# gloria.net
KiCad netlist of a schematic drawn in EAGLE
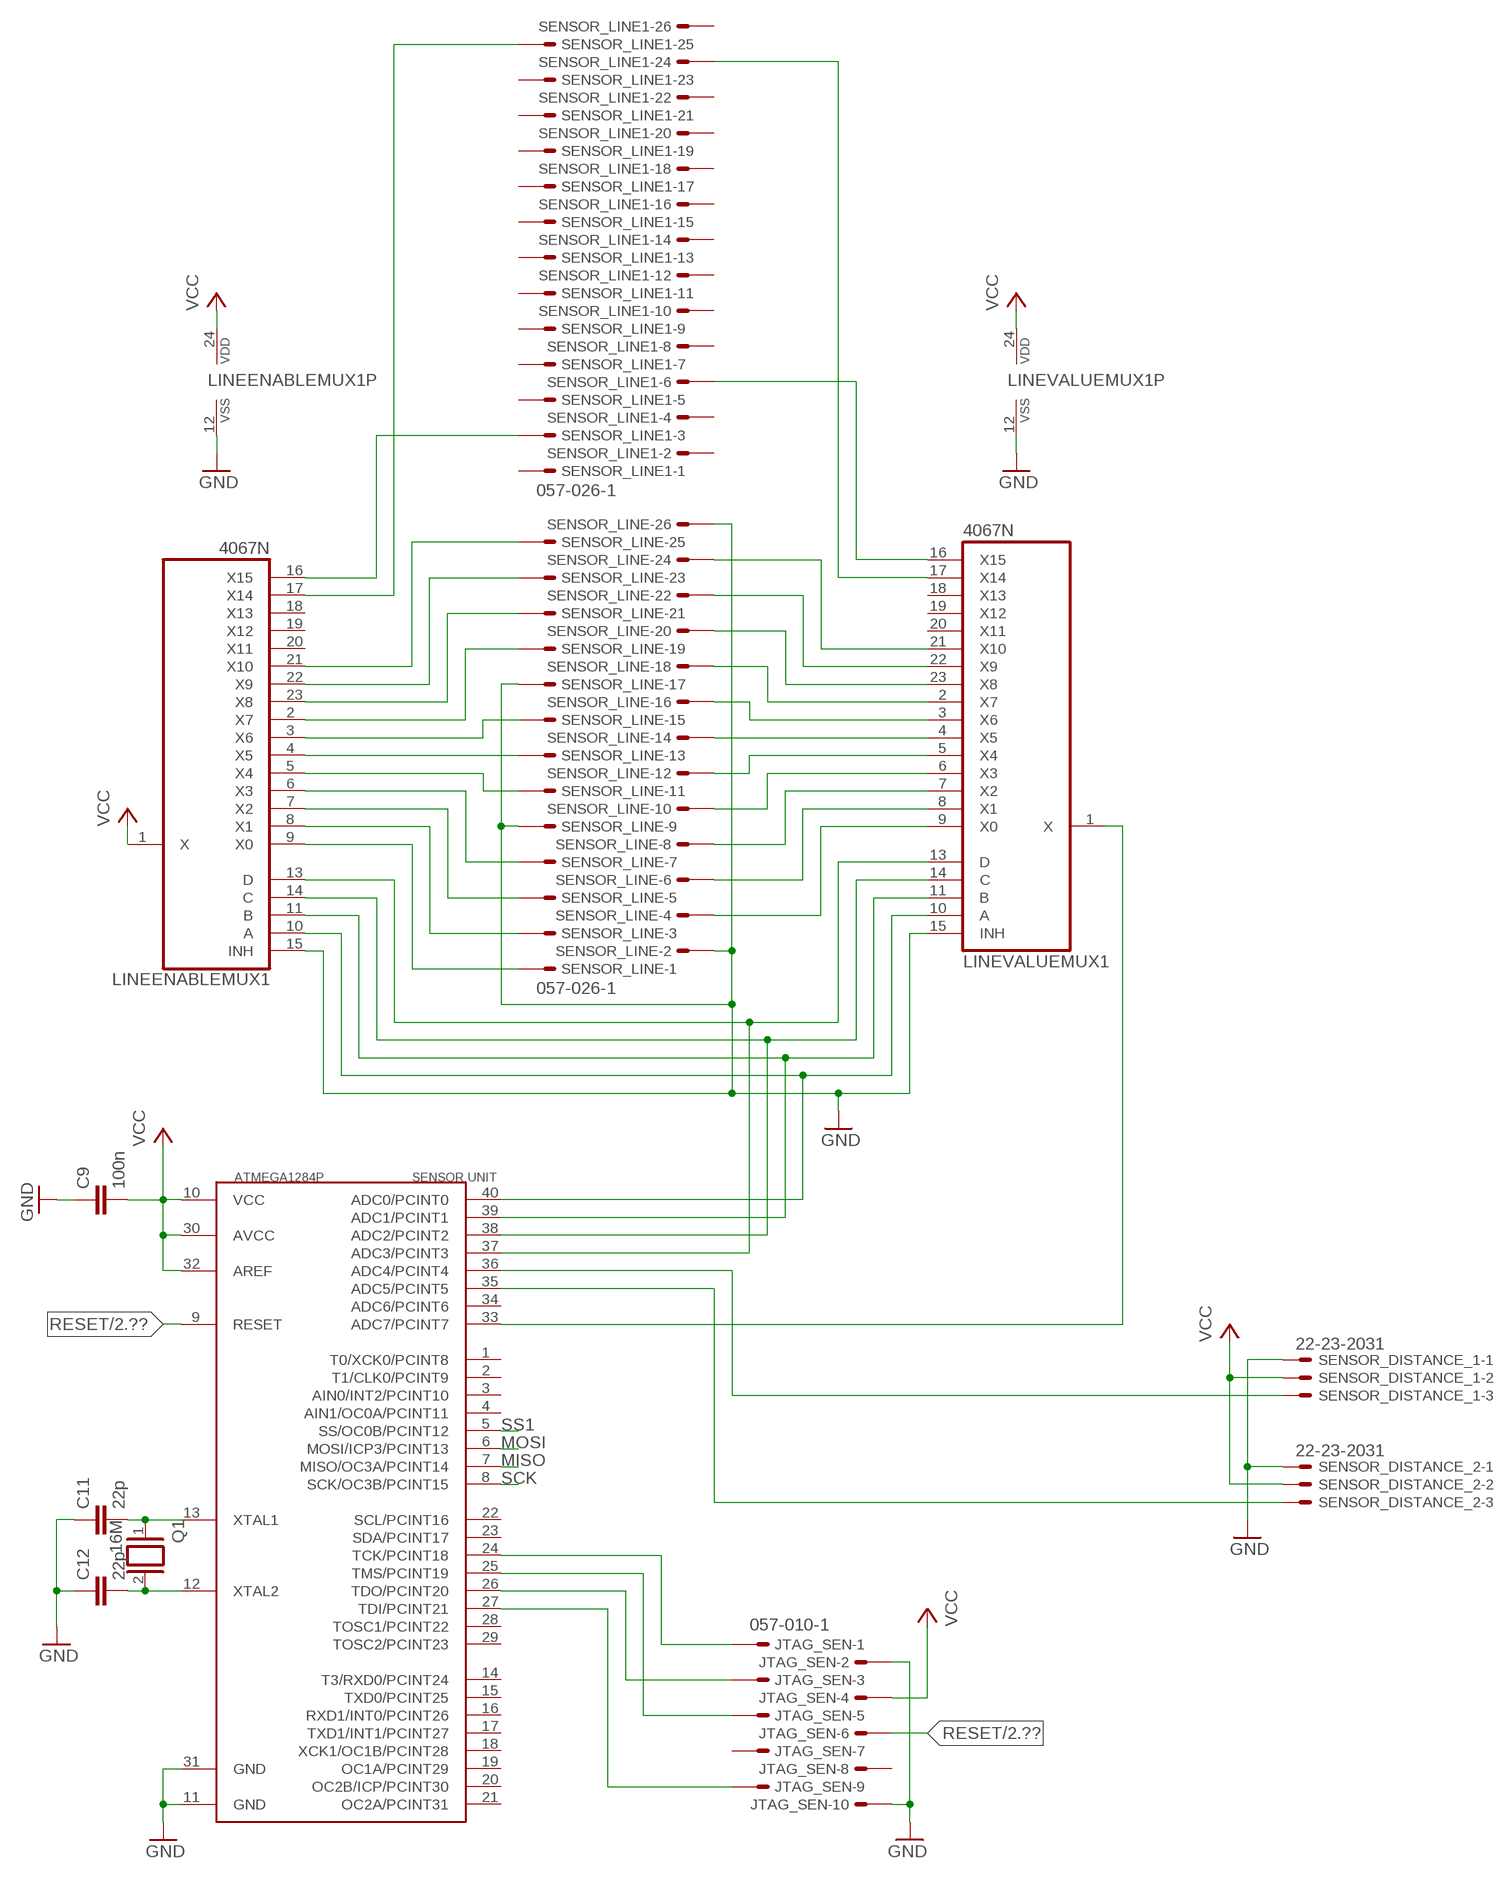
[diagram p0: schematic, sheet 1]
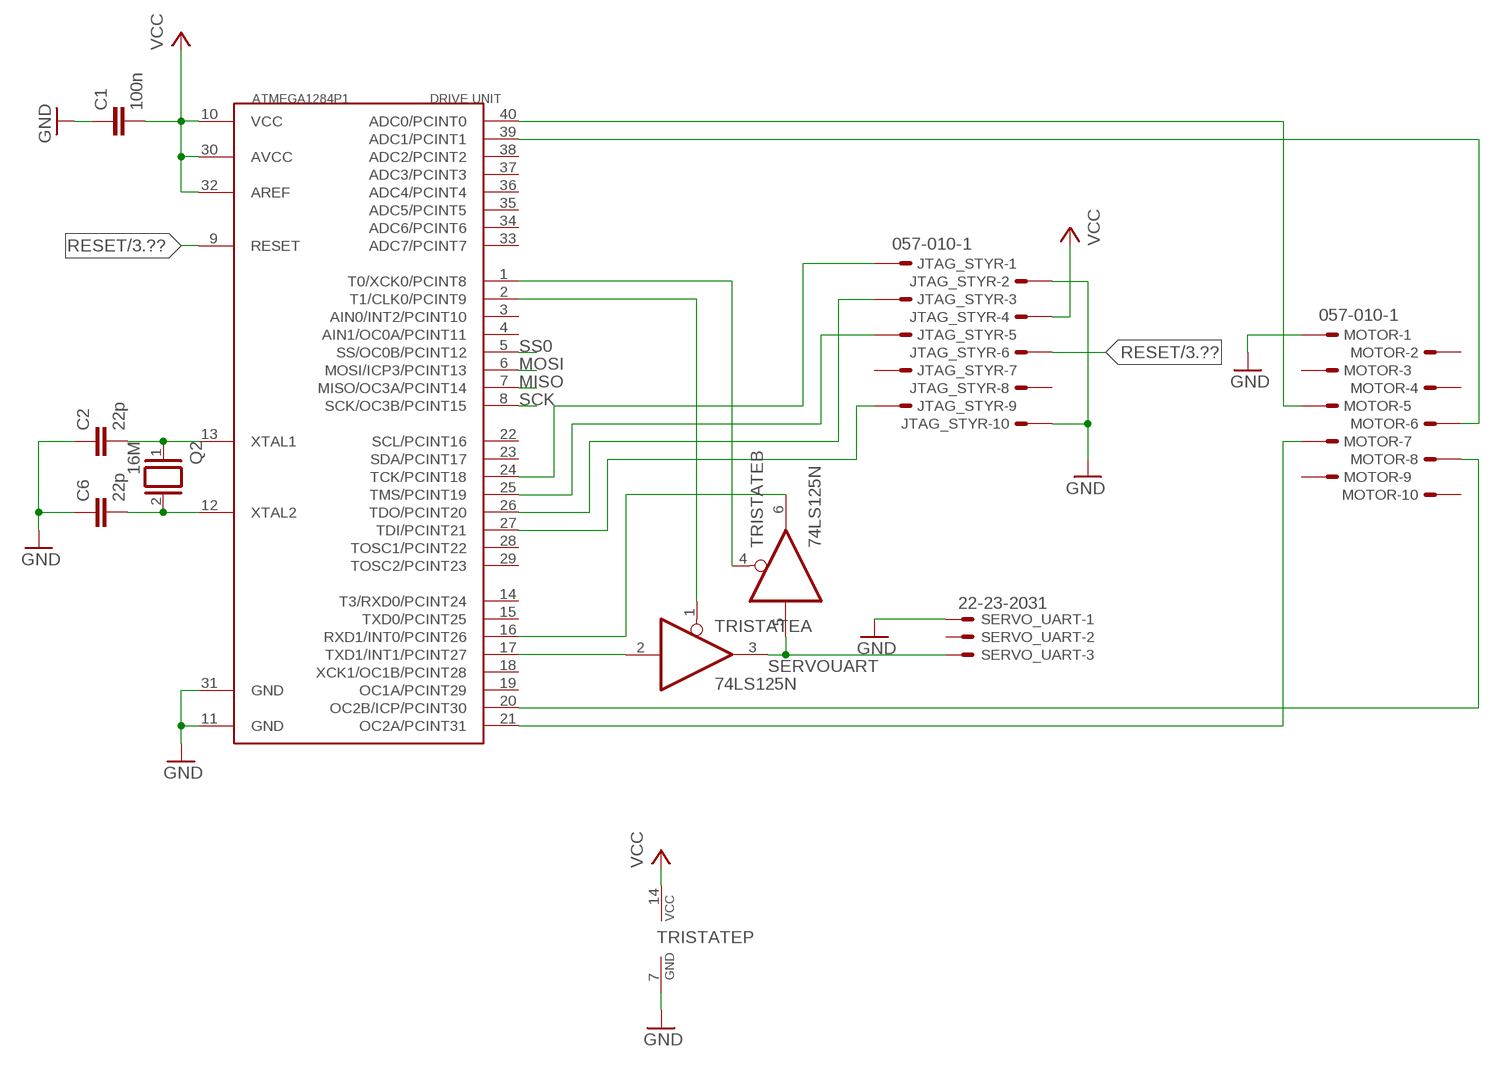
[diagram p1: schematic, sheet 2]
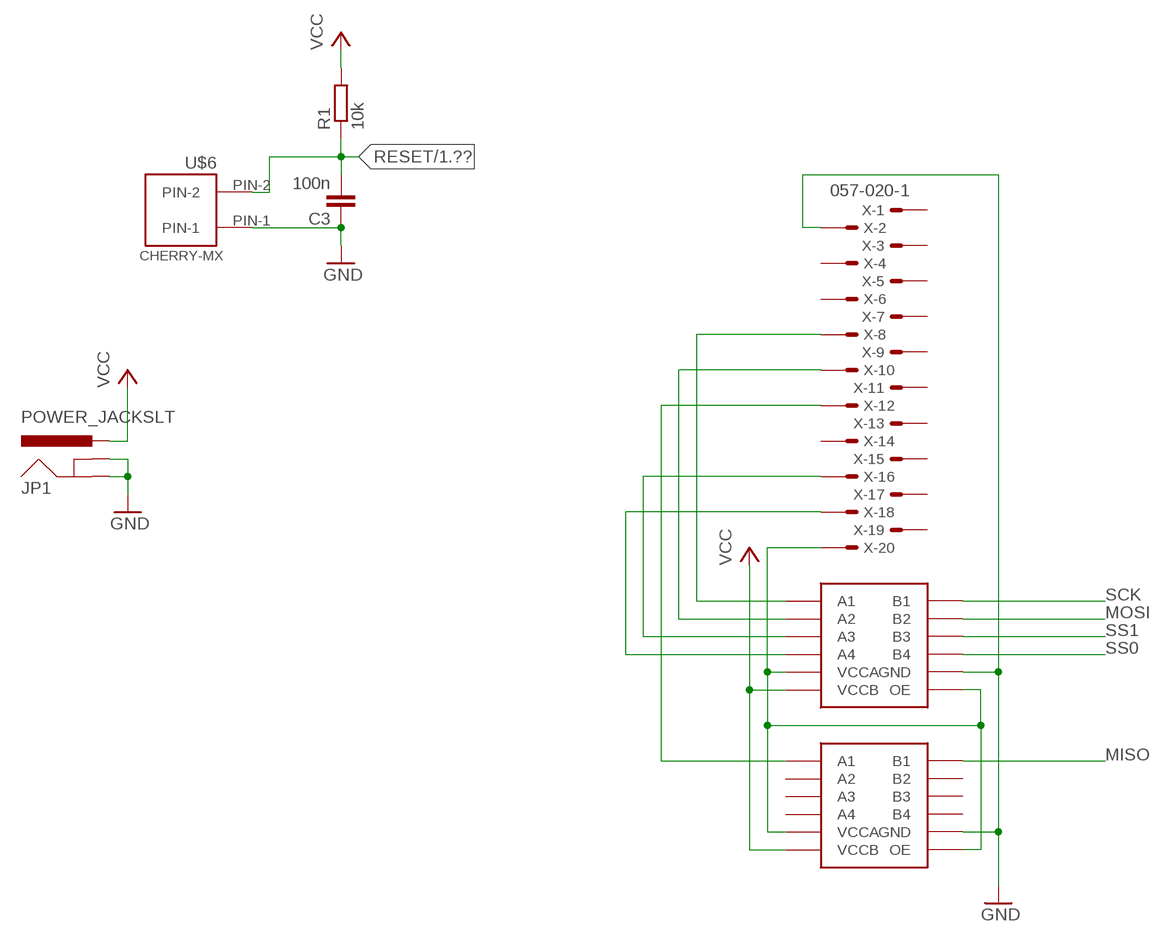
[diagram p2: schematic, sheet 3]

(export (version "E")
  (design (tool "Eeschema 10.0.6"))
  (components
    (comp (ref "ATMEGA1284P")
      (value "SENSOR UNIT")
      (footprint "eagle-import:DIL40")
      (libsource (lib "eagle-import") (part "MEGA1284P"))
    )
    (comp (ref "C9")
      (value "100n")
      (footprint "eagle-import:C025-024X044")
      (libsource (lib "eagle-import") (part "C-EU025-024X044"))
    )
    (comp (ref "C11")
      (value "22p")
      (footprint "eagle-import:C025-024X044")
      (libsource (lib "eagle-import") (part "C-EU025-024X044"))
    )
    (comp (ref "C12")
      (value "22p")
      (footprint "eagle-import:C025-024X044")
      (libsource (lib "eagle-import") (part "C-EU025-024X044"))
    )
    (comp (ref "JTAG_SEN")
      (value "057-010-1")
      (footprint "eagle-import:057-010-1")
      (libsource (lib "eagle-import") (part "057-010-1"))
    )
    (comp (ref "LINEENABLEMUX1")
      (value "4067N")
      (footprint "eagle-import:DIL24-6")
      (libsource (lib "eagle-import") (part "4067N"))
    )
    (comp (ref "LINEVALUEMUX1")
      (value "4067N")
      (footprint "eagle-import:DIL24-6")
      (libsource (lib "eagle-import") (part "4067N"))
    )
    (comp (ref "Q1")
      (value "16M")
      (footprint "eagle-import:QS")
      (libsource (lib "eagle-import") (part "XTAL/S"))
    )
    (comp (ref "SENSOR_DISTANCE_1")
      (value "22-23-2031")
      (footprint "eagle-import:22-23-2031")
      (fields (field (name "MF") "MOLEX"))
      (libsource (lib "eagle-import") (part "22-23-2031"))
    )
    (comp (ref "SENSOR_DISTANCE_2")
      (value "22-23-2031")
      (footprint "eagle-import:22-23-2031")
      (fields (field (name "MF") "MOLEX"))
      (libsource (lib "eagle-import") (part "22-23-2031"))
    )
    (comp (ref "SENSOR_LINE")
      (value "057-026-1")
      (footprint "eagle-import:057-026-1")
      (libsource (lib "eagle-import") (part "057-026-1"))
    )
    (comp (ref "SENSOR_LINE1")
      (value "057-026-1")
      (footprint "eagle-import:057-026-1")
      (libsource (lib "eagle-import") (part "057-026-1"))
    )
    (comp (ref "ATMEGA1284P1")
      (value "DRIVE UNIT")
      (footprint "eagle-import:DIL40")
      (libsource (lib "eagle-import") (part "MEGA1284P"))
    )
    (comp (ref "C1")
      (value "100n")
      (footprint "eagle-import:C025-024X044")
      (libsource (lib "eagle-import") (part "C-EU025-024X044"))
    )
    (comp (ref "C2")
      (value "22p")
      (footprint "eagle-import:C025-024X044")
      (libsource (lib "eagle-import") (part "C-EU025-024X044"))
    )
    (comp (ref "C6")
      (value "22p")
      (footprint "eagle-import:C025-024X044")
      (libsource (lib "eagle-import") (part "C-EU025-024X044"))
    )
    (comp (ref "JTAG_STYR")
      (value "057-010-1")
      (footprint "eagle-import:057-010-1")
      (libsource (lib "eagle-import") (part "057-010-1"))
    )
    (comp (ref "MOTOR")
      (value "057-010-1")
      (footprint "eagle-import:057-010-1")
      (libsource (lib "eagle-import") (part "057-010-1"))
    )
    (comp (ref "Q2")
      (value "16M")
      (footprint "eagle-import:QS")
      (libsource (lib "eagle-import") (part "XTAL/S"))
    )
    (comp (ref "SERVO_UART")
      (value "22-23-2031")
      (footprint "eagle-import:22-23-2031")
      (fields (field (name "MF") "MOLEX"))
      (libsource (lib "eagle-import") (part "22-23-2031"))
    )
    (comp (ref "TRISTATE")
      (value "74LS125N")
      (footprint "eagle-import:DIL14")
      (libsource (lib "eagle-import") (part "74125NLS"))
    )
    (comp (ref "C3")
      (value "100n")
      (footprint "eagle-import:C025-024X044")
      (libsource (lib "eagle-import") (part "C-EU025-024X044"))
    )
    (comp (ref "JP1")
      (value "POWER_JACKSLT")
      (footprint "eagle-import:POWER_JACK_SLOT")
      (libsource (lib "eagle-import") (part "POWER_JACKSLT"))
    )
    (comp (ref "R1")
      (value "10k")
      (footprint "eagle-import:0204V")
      (libsource (lib "eagle-import") (part "R-EU_0204/2V"))
    )
    (comp (ref "U$1")
      (value "TXB0104SOIC(D)")
      (footprint "eagle-import:TXB0104")
      (libsource (lib "eagle-import") (part "TXB0104SOIC(D)"))
    )
    (comp (ref "U$2")
      (value "TXB0104SOIC(D)")
      (footprint "eagle-import:TXB0104")
      (libsource (lib "eagle-import") (part "TXB0104SOIC(D)"))
    )
    (comp (ref "U$6")
      (value "CHERRY-MX-I")
      (footprint "eagle-import:CHERRY-MX-I")
      (libsource (lib "eagle-import") (part "CHERRY-MX-I"))
    )
    (comp (ref "X")
      (value "057-020-1")
      (footprint "eagle-import:057-020-1")
      (libsource (lib "eagle-import") (part "057-020-1"))
    )
  )
  (nets
    (net (code "1") (name "GND") (class "Default")
      (node (ref "ATMEGA1284P") (pin "11") (pinfunction "GND_11") (pintype "bidirectional"))
      (node (ref "ATMEGA1284P") (pin "31") (pinfunction "GND_31") (pintype "bidirectional"))
      (node (ref "ATMEGA1284P1") (pin "11") (pinfunction "GND_11") (pintype "bidirectional"))
      (node (ref "ATMEGA1284P1") (pin "31") (pinfunction "GND_31") (pintype "bidirectional"))
      (node (ref "C1") (pin "1") (pinfunction "1_1") (pintype "passive"))
      (node (ref "C11") (pin "1") (pinfunction "1_1") (pintype "passive"))
      (node (ref "C12") (pin "1") (pinfunction "1_1") (pintype "passive"))
      (node (ref "C2") (pin "1") (pinfunction "1_1") (pintype "passive"))
      (node (ref "C3") (pin "1") (pinfunction "1_1") (pintype "passive"))
      (node (ref "C6") (pin "1") (pinfunction "1_1") (pintype "passive"))
      (node (ref "C9") (pin "1") (pinfunction "1_1") (pintype "passive"))
      (node (ref "JP1") (pin "GND@1") (pinfunction "GNDBREAK_GND@1") (pintype "bidirectional"))
      (node (ref "JP1") (pin "GND@2") (pinfunction "GND_GND@2") (pintype "bidirectional"))
      (node (ref "JTAG_SEN") (pin "10") (pinfunction "S_10") (pintype "passive"))
      (node (ref "JTAG_SEN") (pin "2") (pinfunction "S_2") (pintype "passive"))
      (node (ref "JTAG_STYR") (pin "10") (pinfunction "S_10") (pintype "passive"))
      (node (ref "JTAG_STYR") (pin "2") (pinfunction "S_2") (pintype "passive"))
      (node (ref "LINEENABLEMUX1") (pin "12") (pinfunction "VSS_12") (pintype "power_in"))
      (node (ref "LINEENABLEMUX1") (pin "15") (pinfunction "INH_15") (pintype "input"))
      (node (ref "LINEVALUEMUX1") (pin "12") (pinfunction "VSS_12") (pintype "power_in"))
      (node (ref "LINEVALUEMUX1") (pin "15") (pinfunction "INH_15") (pintype "input"))
      (node (ref "MOTOR") (pin "1") (pinfunction "S_1") (pintype "passive"))
      (node (ref "SENSOR_DISTANCE_1") (pin "1") (pinfunction "S_1") (pintype "passive"))
      (node (ref "SENSOR_DISTANCE_2") (pin "1") (pinfunction "S_1") (pintype "passive"))
      (node (ref "SENSOR_LINE") (pin "17") (pinfunction "S_17") (pintype "passive"))
      (node (ref "SENSOR_LINE") (pin "2") (pinfunction "S_2") (pintype "passive"))
      (node (ref "SENSOR_LINE") (pin "26") (pinfunction "S_26") (pintype "passive"))
      (node (ref "SENSOR_LINE") (pin "9") (pinfunction "S_9") (pintype "passive"))
      (node (ref "SERVO_UART") (pin "1") (pinfunction "S_1") (pintype "passive"))
      (node (ref "TRISTATE") (pin "7") (pinfunction "GND_7") (pintype "power_in"))
      (node (ref "U$1") (pin "P$7") (pinfunction "GND_P$7") (pintype "bidirectional"))
      (node (ref "U$2") (pin "P$7") (pinfunction "GND_P$7") (pintype "bidirectional"))
      (node (ref "U$6") (pin "PIN-1") (pinfunction "PIN-1_PIN-1") (pintype "bidirectional"))
      (node (ref "X") (pin "2") (pinfunction "S_2") (pintype "passive"))
    )
    (net (code "2") (name "MISO") (class "Default")
      (node (ref "ATMEGA1284P") (pin "7") (pinfunction "MISO/OC3A/PCINT14_7") (pintype "bidirectional"))
      (node (ref "ATMEGA1284P1") (pin "7") (pinfunction "MISO/OC3A/PCINT14_7") (pintype "bidirectional"))
      (node (ref "U$2") (pin "P$13") (pinfunction "B1_P$13") (pintype "bidirectional"))
    )
    (net (code "3") (name "MOSI") (class "Default")
      (node (ref "ATMEGA1284P") (pin "6") (pinfunction "MOSI/ICP3/PCINT13_6") (pintype "bidirectional"))
      (node (ref "ATMEGA1284P1") (pin "6") (pinfunction "MOSI/ICP3/PCINT13_6") (pintype "bidirectional"))
      (node (ref "U$1") (pin "P$12") (pinfunction "B2_P$12") (pintype "bidirectional"))
    )
    (net (code "4") (name "Net-(ATMEGA1284P-ADC0{slash}PCINT0)") (class "Default")
      (node (ref "ATMEGA1284P") (pin "40") (pinfunction "ADC0/PCINT0_40") (pintype "bidirectional"))
      (node (ref "LINEENABLEMUX1") (pin "10") (pinfunction "A_10") (pintype "input"))
      (node (ref "LINEVALUEMUX1") (pin "10") (pinfunction "A_10") (pintype "input"))
    )
    (net (code "5") (name "Net-(ATMEGA1284P-ADC1{slash}PCINT1)") (class "Default")
      (node (ref "ATMEGA1284P") (pin "39") (pinfunction "ADC1/PCINT1_39") (pintype "bidirectional"))
      (node (ref "LINEENABLEMUX1") (pin "11") (pinfunction "B_11") (pintype "input"))
      (node (ref "LINEVALUEMUX1") (pin "11") (pinfunction "B_11") (pintype "input"))
    )
    (net (code "6") (name "Net-(ATMEGA1284P-ADC2{slash}PCINT2)") (class "Default")
      (node (ref "ATMEGA1284P") (pin "38") (pinfunction "ADC2/PCINT2_38") (pintype "bidirectional"))
      (node (ref "LINEENABLEMUX1") (pin "14") (pinfunction "C_14") (pintype "input"))
      (node (ref "LINEVALUEMUX1") (pin "14") (pinfunction "C_14") (pintype "input"))
    )
    (net (code "7") (name "Net-(ATMEGA1284P-ADC3{slash}PCINT3)") (class "Default")
      (node (ref "ATMEGA1284P") (pin "37") (pinfunction "ADC3/PCINT3_37") (pintype "bidirectional"))
      (node (ref "LINEENABLEMUX1") (pin "13") (pinfunction "D_13") (pintype "input"))
      (node (ref "LINEVALUEMUX1") (pin "13") (pinfunction "D_13") (pintype "input"))
    )
    (net (code "8") (name "Net-(ATMEGA1284P-ADC4{slash}PCINT4)") (class "Default")
      (node (ref "ATMEGA1284P") (pin "36") (pinfunction "ADC4/PCINT4_36") (pintype "bidirectional"))
      (node (ref "SENSOR_DISTANCE_1") (pin "3") (pinfunction "S_3") (pintype "passive"))
    )
    (net (code "9") (name "Net-(ATMEGA1284P-ADC5{slash}PCINT5)") (class "Default")
      (node (ref "ATMEGA1284P") (pin "35") (pinfunction "ADC5/PCINT5_35") (pintype "bidirectional"))
      (node (ref "SENSOR_DISTANCE_2") (pin "3") (pinfunction "S_3") (pintype "passive"))
    )
    (net (code "10") (name "Net-(ATMEGA1284P-ADC7{slash}PCINT7)") (class "Default")
      (node (ref "ATMEGA1284P") (pin "33") (pinfunction "ADC7/PCINT7_33") (pintype "bidirectional"))
      (node (ref "LINEVALUEMUX1") (pin "1") (pinfunction "X_1") (pintype "output"))
    )
    (net (code "11") (name "Net-(ATMEGA1284P-TCK{slash}PCINT18)") (class "Default")
      (node (ref "ATMEGA1284P") (pin "24") (pinfunction "TCK/PCINT18_24") (pintype "bidirectional"))
      (node (ref "JTAG_SEN") (pin "1") (pinfunction "S_1") (pintype "passive"))
    )
    (net (code "12") (name "Net-(ATMEGA1284P-TDI{slash}PCINT21)") (class "Default")
      (node (ref "ATMEGA1284P") (pin "27") (pinfunction "TDI/PCINT21_27") (pintype "bidirectional"))
      (node (ref "JTAG_SEN") (pin "9") (pinfunction "S_9") (pintype "passive"))
    )
    (net (code "13") (name "Net-(ATMEGA1284P-TDO{slash}PCINT20)") (class "Default")
      (node (ref "ATMEGA1284P") (pin "26") (pinfunction "TDO/PCINT20_26") (pintype "bidirectional"))
      (node (ref "JTAG_SEN") (pin "3") (pinfunction "S_3") (pintype "passive"))
    )
    (net (code "14") (name "Net-(ATMEGA1284P-TMS{slash}PCINT19)") (class "Default")
      (node (ref "ATMEGA1284P") (pin "25") (pinfunction "TMS/PCINT19_25") (pintype "bidirectional"))
      (node (ref "JTAG_SEN") (pin "5") (pinfunction "S_5") (pintype "passive"))
    )
    (net (code "15") (name "Net-(ATMEGA1284P-XTAL1)") (class "Default")
      (node (ref "ATMEGA1284P") (pin "13") (pinfunction "XTAL1_13") (pintype "bidirectional"))
      (node (ref "C11") (pin "2") (pinfunction "2_2") (pintype "passive"))
      (node (ref "Q1") (pin "1") (pinfunction "1_1") (pintype "passive"))
    )
    (net (code "16") (name "Net-(ATMEGA1284P-XTAL2)") (class "Default")
      (node (ref "ATMEGA1284P") (pin "12") (pinfunction "XTAL2_12") (pintype "bidirectional"))
      (node (ref "C12") (pin "2") (pinfunction "2_2") (pintype "passive"))
      (node (ref "Q1") (pin "2") (pinfunction "2_2") (pintype "passive"))
    )
    (net (code "17") (name "Net-(ATMEGA1284P1-ADC0{slash}PCINT0)") (class "Default")
      (node (ref "ATMEGA1284P1") (pin "40") (pinfunction "ADC0/PCINT0_40") (pintype "bidirectional"))
      (node (ref "MOTOR") (pin "5") (pinfunction "S_5") (pintype "passive"))
    )
    (net (code "18") (name "Net-(ATMEGA1284P1-ADC1{slash}PCINT1)") (class "Default")
      (node (ref "ATMEGA1284P1") (pin "39") (pinfunction "ADC1/PCINT1_39") (pintype "bidirectional"))
      (node (ref "MOTOR") (pin "6") (pinfunction "S_6") (pintype "passive"))
    )
    (net (code "19") (name "Net-(ATMEGA1284P1-OC2A{slash}PCINT31)") (class "Default")
      (node (ref "ATMEGA1284P1") (pin "21") (pinfunction "OC2A/PCINT31_21") (pintype "bidirectional"))
      (node (ref "MOTOR") (pin "7") (pinfunction "S_7") (pintype "passive"))
    )
    (net (code "20") (name "Net-(ATMEGA1284P1-OC2B{slash}ICP{slash}PCINT30)") (class "Default")
      (node (ref "ATMEGA1284P1") (pin "20") (pinfunction "OC2B/ICP/PCINT30_20") (pintype "bidirectional"))
      (node (ref "MOTOR") (pin "8") (pinfunction "S_8") (pintype "passive"))
    )
    (net (code "21") (name "Net-(ATMEGA1284P1-RXD1{slash}INT0{slash}PCINT26)") (class "Default")
      (node (ref "ATMEGA1284P1") (pin "16") (pinfunction "RXD1/INT0/PCINT26_16") (pintype "bidirectional"))
      (node (ref "TRISTATE") (pin "6") (pinfunction "O_6") (pintype "tri_state"))
    )
    (net (code "22") (name "Net-(ATMEGA1284P1-T0{slash}XCK0{slash}PCINT8)") (class "Default")
      (node (ref "ATMEGA1284P1") (pin "1") (pinfunction "T0/XCK0/PCINT8_1") (pintype "bidirectional"))
      (node (ref "TRISTATE") (pin "4") (pinfunction "OE_4") (pintype "input"))
    )
    (net (code "23") (name "Net-(ATMEGA1284P1-T1{slash}CLK0{slash}PCINT9)") (class "Default")
      (node (ref "ATMEGA1284P1") (pin "2") (pinfunction "T1/CLK0/PCINT9_2") (pintype "bidirectional"))
      (node (ref "TRISTATE") (pin "1") (pinfunction "OE_1") (pintype "input"))
    )
    (net (code "24") (name "Net-(ATMEGA1284P1-TCK{slash}PCINT18)") (class "Default")
      (node (ref "ATMEGA1284P1") (pin "24") (pinfunction "TCK/PCINT18_24") (pintype "bidirectional"))
      (node (ref "JTAG_STYR") (pin "1") (pinfunction "S_1") (pintype "passive"))
    )
    (net (code "25") (name "Net-(ATMEGA1284P1-TDI{slash}PCINT21)") (class "Default")
      (node (ref "ATMEGA1284P1") (pin "27") (pinfunction "TDI/PCINT21_27") (pintype "bidirectional"))
      (node (ref "JTAG_STYR") (pin "9") (pinfunction "S_9") (pintype "passive"))
    )
    (net (code "26") (name "Net-(ATMEGA1284P1-TDO{slash}PCINT20)") (class "Default")
      (node (ref "ATMEGA1284P1") (pin "26") (pinfunction "TDO/PCINT20_26") (pintype "bidirectional"))
      (node (ref "JTAG_STYR") (pin "3") (pinfunction "S_3") (pintype "passive"))
    )
    (net (code "27") (name "Net-(ATMEGA1284P1-TMS{slash}PCINT19)") (class "Default")
      (node (ref "ATMEGA1284P1") (pin "25") (pinfunction "TMS/PCINT19_25") (pintype "bidirectional"))
      (node (ref "JTAG_STYR") (pin "5") (pinfunction "S_5") (pintype "passive"))
    )
    (net (code "28") (name "Net-(ATMEGA1284P1-TXD1{slash}INT1{slash}PCINT27)") (class "Default")
      (node (ref "ATMEGA1284P1") (pin "17") (pinfunction "TXD1/INT1/PCINT27_17") (pintype "bidirectional"))
      (node (ref "TRISTATE") (pin "2") (pinfunction "I_2") (pintype "input"))
    )
    (net (code "29") (name "Net-(ATMEGA1284P1-XTAL1)") (class "Default")
      (node (ref "ATMEGA1284P1") (pin "13") (pinfunction "XTAL1_13") (pintype "bidirectional"))
      (node (ref "C2") (pin "2") (pinfunction "2_2") (pintype "passive"))
      (node (ref "Q2") (pin "1") (pinfunction "1_1") (pintype "passive"))
    )
    (net (code "30") (name "Net-(ATMEGA1284P1-XTAL2)") (class "Default")
      (node (ref "ATMEGA1284P1") (pin "12") (pinfunction "XTAL2_12") (pintype "bidirectional"))
      (node (ref "C6") (pin "2") (pinfunction "2_2") (pintype "passive"))
      (node (ref "Q2") (pin "2") (pinfunction "2_2") (pintype "passive"))
    )
    (net (code "31") (name "Net-(LINEENABLEMUX1A-X0)") (class "Default")
      (node (ref "LINEENABLEMUX1") (pin "9") (pinfunction "X0_9") (pintype "input"))
      (node (ref "SENSOR_LINE") (pin "1") (pinfunction "S_1") (pintype "passive"))
    )
    (net (code "32") (name "Net-(LINEENABLEMUX1A-X1)") (class "Default")
      (node (ref "LINEENABLEMUX1") (pin "8") (pinfunction "X1_8") (pintype "input"))
      (node (ref "SENSOR_LINE") (pin "3") (pinfunction "S_3") (pintype "passive"))
    )
    (net (code "33") (name "Net-(LINEENABLEMUX1A-X2)") (class "Default")
      (node (ref "LINEENABLEMUX1") (pin "7") (pinfunction "X2_7") (pintype "input"))
      (node (ref "SENSOR_LINE") (pin "5") (pinfunction "S_5") (pintype "passive"))
    )
    (net (code "34") (name "Net-(LINEENABLEMUX1A-X3)") (class "Default")
      (node (ref "LINEENABLEMUX1") (pin "6") (pinfunction "X3_6") (pintype "input"))
      (node (ref "SENSOR_LINE") (pin "7") (pinfunction "S_7") (pintype "passive"))
    )
    (net (code "35") (name "Net-(LINEENABLEMUX1A-X4)") (class "Default")
      (node (ref "LINEENABLEMUX1") (pin "5") (pinfunction "X4_5") (pintype "input"))
      (node (ref "SENSOR_LINE") (pin "11") (pinfunction "S_11") (pintype "passive"))
    )
    (net (code "36") (name "Net-(LINEENABLEMUX1A-X5)") (class "Default")
      (node (ref "LINEENABLEMUX1") (pin "4") (pinfunction "X5_4") (pintype "input"))
      (node (ref "SENSOR_LINE") (pin "13") (pinfunction "S_13") (pintype "passive"))
    )
    (net (code "37") (name "Net-(LINEENABLEMUX1A-X6)") (class "Default")
      (node (ref "LINEENABLEMUX1") (pin "3") (pinfunction "X6_3") (pintype "input"))
      (node (ref "SENSOR_LINE") (pin "15") (pinfunction "S_15") (pintype "passive"))
    )
    (net (code "38") (name "Net-(LINEENABLEMUX1A-X7)") (class "Default")
      (node (ref "LINEENABLEMUX1") (pin "2") (pinfunction "X7_2") (pintype "input"))
      (node (ref "SENSOR_LINE") (pin "19") (pinfunction "S_19") (pintype "passive"))
    )
    (net (code "39") (name "Net-(LINEENABLEMUX1A-X8)") (class "Default")
      (node (ref "LINEENABLEMUX1") (pin "23") (pinfunction "X8_23") (pintype "input"))
      (node (ref "SENSOR_LINE") (pin "21") (pinfunction "S_21") (pintype "passive"))
    )
    (net (code "40") (name "Net-(LINEENABLEMUX1A-X9)") (class "Default")
      (node (ref "LINEENABLEMUX1") (pin "22") (pinfunction "X9_22") (pintype "input"))
      (node (ref "SENSOR_LINE") (pin "23") (pinfunction "S_23") (pintype "passive"))
    )
    (net (code "41") (name "Net-(LINEENABLEMUX1A-X10)") (class "Default")
      (node (ref "LINEENABLEMUX1") (pin "21") (pinfunction "X10_21") (pintype "input"))
      (node (ref "SENSOR_LINE") (pin "25") (pinfunction "S_25") (pintype "passive"))
    )
    (net (code "42") (name "Net-(LINEENABLEMUX1A-X14)") (class "Default")
      (node (ref "LINEENABLEMUX1") (pin "17") (pinfunction "X14_17") (pintype "input"))
      (node (ref "SENSOR_LINE1") (pin "25") (pinfunction "S_25") (pintype "passive"))
    )
    (net (code "43") (name "Net-(LINEENABLEMUX1A-X15)") (class "Default")
      (node (ref "LINEENABLEMUX1") (pin "16") (pinfunction "X15_16") (pintype "input"))
      (node (ref "SENSOR_LINE1") (pin "3") (pinfunction "S_3") (pintype "passive"))
    )
    (net (code "44") (name "Net-(LINEVALUEMUX1A-X0)") (class "Default")
      (node (ref "LINEVALUEMUX1") (pin "9") (pinfunction "X0_9") (pintype "input"))
      (node (ref "SENSOR_LINE") (pin "4") (pinfunction "S_4") (pintype "passive"))
    )
    (net (code "45") (name "Net-(LINEVALUEMUX1A-X1)") (class "Default")
      (node (ref "LINEVALUEMUX1") (pin "8") (pinfunction "X1_8") (pintype "input"))
      (node (ref "SENSOR_LINE") (pin "6") (pinfunction "S_6") (pintype "passive"))
    )
    (net (code "46") (name "Net-(LINEVALUEMUX1A-X2)") (class "Default")
      (node (ref "LINEVALUEMUX1") (pin "7") (pinfunction "X2_7") (pintype "input"))
      (node (ref "SENSOR_LINE") (pin "8") (pinfunction "S_8") (pintype "passive"))
    )
    (net (code "47") (name "Net-(LINEVALUEMUX1A-X3)") (class "Default")
      (node (ref "LINEVALUEMUX1") (pin "6") (pinfunction "X3_6") (pintype "input"))
      (node (ref "SENSOR_LINE") (pin "10") (pinfunction "S_10") (pintype "passive"))
    )
    (net (code "48") (name "Net-(LINEVALUEMUX1A-X4)") (class "Default")
      (node (ref "LINEVALUEMUX1") (pin "5") (pinfunction "X4_5") (pintype "input"))
      (node (ref "SENSOR_LINE") (pin "12") (pinfunction "S_12") (pintype "passive"))
    )
    (net (code "49") (name "Net-(LINEVALUEMUX1A-X5)") (class "Default")
      (node (ref "LINEVALUEMUX1") (pin "4") (pinfunction "X5_4") (pintype "input"))
      (node (ref "SENSOR_LINE") (pin "14") (pinfunction "S_14") (pintype "passive"))
    )
    (net (code "50") (name "Net-(LINEVALUEMUX1A-X6)") (class "Default")
      (node (ref "LINEVALUEMUX1") (pin "3") (pinfunction "X6_3") (pintype "input"))
      (node (ref "SENSOR_LINE") (pin "16") (pinfunction "S_16") (pintype "passive"))
    )
    (net (code "51") (name "Net-(LINEVALUEMUX1A-X7)") (class "Default")
      (node (ref "LINEVALUEMUX1") (pin "2") (pinfunction "X7_2") (pintype "input"))
      (node (ref "SENSOR_LINE") (pin "18") (pinfunction "S_18") (pintype "passive"))
    )
    (net (code "52") (name "Net-(LINEVALUEMUX1A-X8)") (class "Default")
      (node (ref "LINEVALUEMUX1") (pin "23") (pinfunction "X8_23") (pintype "input"))
      (node (ref "SENSOR_LINE") (pin "20") (pinfunction "S_20") (pintype "passive"))
    )
    (net (code "53") (name "Net-(LINEVALUEMUX1A-X9)") (class "Default")
      (node (ref "LINEVALUEMUX1") (pin "22") (pinfunction "X9_22") (pintype "input"))
      (node (ref "SENSOR_LINE") (pin "22") (pinfunction "S_22") (pintype "passive"))
    )
    (net (code "54") (name "Net-(LINEVALUEMUX1A-X10)") (class "Default")
      (node (ref "LINEVALUEMUX1") (pin "21") (pinfunction "X10_21") (pintype "input"))
      (node (ref "SENSOR_LINE") (pin "24") (pinfunction "S_24") (pintype "passive"))
    )
    (net (code "55") (name "Net-(LINEVALUEMUX1A-X14)") (class "Default")
      (node (ref "LINEVALUEMUX1") (pin "17") (pinfunction "X14_17") (pintype "input"))
      (node (ref "SENSOR_LINE1") (pin "24") (pinfunction "S_24") (pintype "passive"))
    )
    (net (code "56") (name "Net-(LINEVALUEMUX1A-X15)") (class "Default")
      (node (ref "LINEVALUEMUX1") (pin "16") (pinfunction "X15_16") (pintype "input"))
      (node (ref "SENSOR_LINE1") (pin "6") (pinfunction "S_6") (pintype "passive"))
    )
    (net (code "57") (name "Net-(U$1-A1)") (class "Default")
      (node (ref "U$1") (pin "P$2") (pinfunction "A1_P$2") (pintype "bidirectional"))
      (node (ref "X") (pin "8") (pinfunction "S_8") (pintype "passive"))
    )
    (net (code "58") (name "Net-(U$1-A2)") (class "Default")
      (node (ref "U$1") (pin "P$3") (pinfunction "A2_P$3") (pintype "bidirectional"))
      (node (ref "X") (pin "10") (pinfunction "S_10") (pintype "passive"))
    )
    (net (code "59") (name "Net-(U$1-A3)") (class "Default")
      (node (ref "U$1") (pin "P$4") (pinfunction "A3_P$4") (pintype "bidirectional"))
      (node (ref "X") (pin "16") (pinfunction "S_16") (pintype "passive"))
    )
    (net (code "60") (name "Net-(U$1-A4)") (class "Default")
      (node (ref "U$1") (pin "P$5") (pinfunction "A4_P$5") (pintype "bidirectional"))
      (node (ref "X") (pin "18") (pinfunction "S_18") (pintype "passive"))
    )
    (net (code "61") (name "Net-(U$1-OE)") (class "Default")
      (node (ref "U$1") (pin "P$1") (pinfunction "VCCA_P$1") (pintype "bidirectional"))
      (node (ref "U$1") (pin "P$8") (pinfunction "OE_P$8") (pintype "bidirectional"))
      (node (ref "U$2") (pin "P$1") (pinfunction "VCCA_P$1") (pintype "bidirectional"))
      (node (ref "U$2") (pin "P$8") (pinfunction "OE_P$8") (pintype "bidirectional"))
      (node (ref "X") (pin "20") (pinfunction "S_20") (pintype "passive"))
    )
    (net (code "62") (name "Net-(U$2-A1)") (class "Default")
      (node (ref "U$2") (pin "P$2") (pinfunction "A1_P$2") (pintype "bidirectional"))
      (node (ref "X") (pin "12") (pinfunction "S_12") (pintype "passive"))
    )
    (net (code "63") (name "RESET") (class "Default")
      (node (ref "ATMEGA1284P") (pin "9") (pinfunction "RESET_9") (pintype "bidirectional"))
      (node (ref "ATMEGA1284P1") (pin "9") (pinfunction "RESET_9") (pintype "bidirectional"))
      (node (ref "C3") (pin "2") (pinfunction "2_2") (pintype "passive"))
      (node (ref "JTAG_SEN") (pin "6") (pinfunction "S_6") (pintype "passive"))
      (node (ref "JTAG_STYR") (pin "6") (pinfunction "S_6") (pintype "passive"))
      (node (ref "R1") (pin "1") (pinfunction "1_1") (pintype "passive"))
      (node (ref "U$6") (pin "PIN-2") (pinfunction "PIN-2_PIN-2") (pintype "bidirectional"))
    )
    (net (code "64") (name "SCK") (class "Default")
      (node (ref "ATMEGA1284P") (pin "8") (pinfunction "SCK/OC3B/PCINT15_8") (pintype "bidirectional"))
      (node (ref "ATMEGA1284P1") (pin "8") (pinfunction "SCK/OC3B/PCINT15_8") (pintype "bidirectional"))
      (node (ref "U$1") (pin "P$13") (pinfunction "B1_P$13") (pintype "bidirectional"))
    )
    (net (code "65") (name "SERVOUART") (class "Default")
      (node (ref "SERVO_UART") (pin "3") (pinfunction "S_3") (pintype "passive"))
      (node (ref "TRISTATE") (pin "3") (pinfunction "O_3") (pintype "tri_state"))
      (node (ref "TRISTATE") (pin "5") (pinfunction "I_5") (pintype "input"))
    )
    (net (code "66") (name "SS0") (class "Default")
      (node (ref "ATMEGA1284P1") (pin "5") (pinfunction "SS/OC0B/PCINT12_5") (pintype "bidirectional"))
      (node (ref "U$1") (pin "P$10") (pinfunction "B4_P$10") (pintype "bidirectional"))
    )
    (net (code "67") (name "SS1") (class "Default")
      (node (ref "ATMEGA1284P") (pin "5") (pinfunction "SS/OC0B/PCINT12_5") (pintype "bidirectional"))
      (node (ref "U$1") (pin "P$11") (pinfunction "B3_P$11") (pintype "bidirectional"))
    )
    (net (code "68") (name "VCC") (class "Default")
      (node (ref "ATMEGA1284P") (pin "10") (pinfunction "VCC_10") (pintype "bidirectional"))
      (node (ref "ATMEGA1284P") (pin "30") (pinfunction "AVCC_30") (pintype "bidirectional"))
      (node (ref "ATMEGA1284P") (pin "32") (pinfunction "AREF_32") (pintype "bidirectional"))
      (node (ref "ATMEGA1284P1") (pin "10") (pinfunction "VCC_10") (pintype "bidirectional"))
      (node (ref "ATMEGA1284P1") (pin "30") (pinfunction "AVCC_30") (pintype "bidirectional"))
      (node (ref "ATMEGA1284P1") (pin "32") (pinfunction "AREF_32") (pintype "bidirectional"))
      (node (ref "C1") (pin "2") (pinfunction "2_2") (pintype "passive"))
      (node (ref "C9") (pin "2") (pinfunction "2_2") (pintype "passive"))
      (node (ref "JP1") (pin "PWR") (pinfunction "PWR_PWR") (pintype "bidirectional"))
      (node (ref "JTAG_SEN") (pin "4") (pinfunction "S_4") (pintype "passive"))
      (node (ref "JTAG_STYR") (pin "4") (pinfunction "S_4") (pintype "passive"))
      (node (ref "LINEENABLEMUX1") (pin "1") (pinfunction "X_1") (pintype "output"))
      (node (ref "LINEENABLEMUX1") (pin "24") (pinfunction "VDD_24") (pintype "power_in"))
      (node (ref "LINEVALUEMUX1") (pin "24") (pinfunction "VDD_24") (pintype "power_in"))
      (node (ref "R1") (pin "2") (pinfunction "2_2") (pintype "passive"))
      (node (ref "SENSOR_DISTANCE_1") (pin "2") (pinfunction "S_2") (pintype "passive"))
      (node (ref "SENSOR_DISTANCE_2") (pin "2") (pinfunction "S_2") (pintype "passive"))
      (node (ref "TRISTATE") (pin "14") (pinfunction "VCC_14") (pintype "power_in"))
      (node (ref "U$1") (pin "P$14") (pinfunction "VCCB_P$14") (pintype "bidirectional"))
      (node (ref "U$2") (pin "P$14") (pinfunction "VCCB_P$14") (pintype "bidirectional"))
    )
    (net (code "69") (name "unconnected-(ATMEGA1284P-ADC6{slash}PCINT6-Pad34)") (class "Default")
      (node (ref "ATMEGA1284P") (pin "34") (pinfunction "ADC6/PCINT6_34") (pintype "bidirectional"))
    )
    (net (code "70") (name "unconnected-(ATMEGA1284P-AIN0{slash}INT2{slash}PCINT10-Pad3)") (class "Default")
      (node (ref "ATMEGA1284P") (pin "3") (pinfunction "AIN0/INT2/PCINT10_3") (pintype "bidirectional"))
    )
    (net (code "71") (name "unconnected-(ATMEGA1284P-AIN1{slash}OC0A{slash}PCINT11-Pad4)") (class "Default")
      (node (ref "ATMEGA1284P") (pin "4") (pinfunction "AIN1/OC0A/PCINT11_4") (pintype "bidirectional"))
    )
    (net (code "72") (name "unconnected-(ATMEGA1284P-OC1A{slash}PCINT29-Pad19)") (class "Default")
      (node (ref "ATMEGA1284P") (pin "19") (pinfunction "OC1A/PCINT29_19") (pintype "bidirectional"))
    )
    (net (code "73") (name "unconnected-(ATMEGA1284P-OC2A{slash}PCINT31-Pad21)") (class "Default")
      (node (ref "ATMEGA1284P") (pin "21") (pinfunction "OC2A/PCINT31_21") (pintype "bidirectional"))
    )
    (net (code "74") (name "unconnected-(ATMEGA1284P-OC2B{slash}ICP{slash}PCINT30-Pad20)") (class "Default")
      (node (ref "ATMEGA1284P") (pin "20") (pinfunction "OC2B/ICP/PCINT30_20") (pintype "bidirectional"))
    )
    (net (code "75") (name "unconnected-(ATMEGA1284P-RXD1{slash}INT0{slash}PCINT26-Pad16)") (class "Default")
      (node (ref "ATMEGA1284P") (pin "16") (pinfunction "RXD1/INT0/PCINT26_16") (pintype "bidirectional"))
    )
    (net (code "76") (name "unconnected-(ATMEGA1284P-SCL{slash}PCINT16-Pad22)") (class "Default")
      (node (ref "ATMEGA1284P") (pin "22") (pinfunction "SCL/PCINT16_22") (pintype "bidirectional"))
    )
    (net (code "77") (name "unconnected-(ATMEGA1284P-SDA{slash}PCINT17-Pad23)") (class "Default")
      (node (ref "ATMEGA1284P") (pin "23") (pinfunction "SDA/PCINT17_23") (pintype "bidirectional"))
    )
    (net (code "78") (name "unconnected-(ATMEGA1284P-T0{slash}XCK0{slash}PCINT8-Pad1)") (class "Default")
      (node (ref "ATMEGA1284P") (pin "1") (pinfunction "T0/XCK0/PCINT8_1") (pintype "bidirectional"))
    )
    (net (code "79") (name "unconnected-(ATMEGA1284P-T1{slash}CLK0{slash}PCINT9-Pad2)") (class "Default")
      (node (ref "ATMEGA1284P") (pin "2") (pinfunction "T1/CLK0/PCINT9_2") (pintype "bidirectional"))
    )
    (net (code "80") (name "unconnected-(ATMEGA1284P-T3{slash}RXD0{slash}PCINT24-Pad14)") (class "Default")
      (node (ref "ATMEGA1284P") (pin "14") (pinfunction "T3/RXD0/PCINT24_14") (pintype "bidirectional"))
    )
    (net (code "81") (name "unconnected-(ATMEGA1284P-TOSC1{slash}PCINT22-Pad28)") (class "Default")
      (node (ref "ATMEGA1284P") (pin "28") (pinfunction "TOSC1/PCINT22_28") (pintype "bidirectional"))
    )
    (net (code "82") (name "unconnected-(ATMEGA1284P-TOSC2{slash}PCINT23-Pad29)") (class "Default")
      (node (ref "ATMEGA1284P") (pin "29") (pinfunction "TOSC2/PCINT23_29") (pintype "bidirectional"))
    )
    (net (code "83") (name "unconnected-(ATMEGA1284P-TXD0{slash}PCINT25-Pad15)") (class "Default")
      (node (ref "ATMEGA1284P") (pin "15") (pinfunction "TXD0/PCINT25_15") (pintype "bidirectional"))
    )
    (net (code "84") (name "unconnected-(ATMEGA1284P-TXD1{slash}INT1{slash}PCINT27-Pad17)") (class "Default")
      (node (ref "ATMEGA1284P") (pin "17") (pinfunction "TXD1/INT1/PCINT27_17") (pintype "bidirectional"))
    )
    (net (code "85") (name "unconnected-(ATMEGA1284P-XCK1{slash}OC1B{slash}PCINT28-Pad18)") (class "Default")
      (node (ref "ATMEGA1284P") (pin "18") (pinfunction "XCK1/OC1B/PCINT28_18") (pintype "bidirectional"))
    )
    (net (code "86") (name "unconnected-(ATMEGA1284P1-ADC2{slash}PCINT2-Pad38)") (class "Default")
      (node (ref "ATMEGA1284P1") (pin "38") (pinfunction "ADC2/PCINT2_38") (pintype "bidirectional"))
    )
    (net (code "87") (name "unconnected-(ATMEGA1284P1-ADC3{slash}PCINT3-Pad37)") (class "Default")
      (node (ref "ATMEGA1284P1") (pin "37") (pinfunction "ADC3/PCINT3_37") (pintype "bidirectional"))
    )
    (net (code "88") (name "unconnected-(ATMEGA1284P1-ADC4{slash}PCINT4-Pad36)") (class "Default")
      (node (ref "ATMEGA1284P1") (pin "36") (pinfunction "ADC4/PCINT4_36") (pintype "bidirectional"))
    )
    (net (code "89") (name "unconnected-(ATMEGA1284P1-ADC5{slash}PCINT5-Pad35)") (class "Default")
      (node (ref "ATMEGA1284P1") (pin "35") (pinfunction "ADC5/PCINT5_35") (pintype "bidirectional"))
    )
    (net (code "90") (name "unconnected-(ATMEGA1284P1-ADC6{slash}PCINT6-Pad34)") (class "Default")
      (node (ref "ATMEGA1284P1") (pin "34") (pinfunction "ADC6/PCINT6_34") (pintype "bidirectional"))
    )
    (net (code "91") (name "unconnected-(ATMEGA1284P1-ADC7{slash}PCINT7-Pad33)") (class "Default")
      (node (ref "ATMEGA1284P1") (pin "33") (pinfunction "ADC7/PCINT7_33") (pintype "bidirectional"))
    )
    (net (code "92") (name "unconnected-(ATMEGA1284P1-AIN0{slash}INT2{slash}PCINT10-Pad3)") (class "Default")
      (node (ref "ATMEGA1284P1") (pin "3") (pinfunction "AIN0/INT2/PCINT10_3") (pintype "bidirectional"))
    )
    (net (code "93") (name "unconnected-(ATMEGA1284P1-AIN1{slash}OC0A{slash}PCINT11-Pad4)") (class "Default")
      (node (ref "ATMEGA1284P1") (pin "4") (pinfunction "AIN1/OC0A/PCINT11_4") (pintype "bidirectional"))
    )
    (net (code "94") (name "unconnected-(ATMEGA1284P1-OC1A{slash}PCINT29-Pad19)") (class "Default")
      (node (ref "ATMEGA1284P1") (pin "19") (pinfunction "OC1A/PCINT29_19") (pintype "bidirectional"))
    )
    (net (code "95") (name "unconnected-(ATMEGA1284P1-SCL{slash}PCINT16-Pad22)") (class "Default")
      (node (ref "ATMEGA1284P1") (pin "22") (pinfunction "SCL/PCINT16_22") (pintype "bidirectional"))
    )
    (net (code "96") (name "unconnected-(ATMEGA1284P1-SDA{slash}PCINT17-Pad23)") (class "Default")
      (node (ref "ATMEGA1284P1") (pin "23") (pinfunction "SDA/PCINT17_23") (pintype "bidirectional"))
    )
    (net (code "97") (name "unconnected-(ATMEGA1284P1-T3{slash}RXD0{slash}PCINT24-Pad14)") (class "Default")
      (node (ref "ATMEGA1284P1") (pin "14") (pinfunction "T3/RXD0/PCINT24_14") (pintype "bidirectional"))
    )
    (net (code "98") (name "unconnected-(ATMEGA1284P1-TOSC1{slash}PCINT22-Pad28)") (class "Default")
      (node (ref "ATMEGA1284P1") (pin "28") (pinfunction "TOSC1/PCINT22_28") (pintype "bidirectional"))
    )
    (net (code "99") (name "unconnected-(ATMEGA1284P1-TOSC2{slash}PCINT23-Pad29)") (class "Default")
      (node (ref "ATMEGA1284P1") (pin "29") (pinfunction "TOSC2/PCINT23_29") (pintype "bidirectional"))
    )
    (net (code "100") (name "unconnected-(ATMEGA1284P1-TXD0{slash}PCINT25-Pad15)") (class "Default")
      (node (ref "ATMEGA1284P1") (pin "15") (pinfunction "TXD0/PCINT25_15") (pintype "bidirectional"))
    )
    (net (code "101") (name "unconnected-(ATMEGA1284P1-XCK1{slash}OC1B{slash}PCINT28-Pad18)") (class "Default")
      (node (ref "ATMEGA1284P1") (pin "18") (pinfunction "XCK1/OC1B/PCINT28_18") (pintype "bidirectional"))
    )
    (net (code "102") (name "unconnected-(JTAG_SENH-S-Pad7)") (class "Default")
      (node (ref "JTAG_SEN") (pin "7") (pinfunction "S_7") (pintype "passive"))
    )
    (net (code "103") (name "unconnected-(JTAG_SENI-S-Pad8)") (class "Default")
      (node (ref "JTAG_SEN") (pin "8") (pinfunction "S_8") (pintype "passive"))
    )
    (net (code "104") (name "unconnected-(JTAG_STYRH-S-Pad7)") (class "Default")
      (node (ref "JTAG_STYR") (pin "7") (pinfunction "S_7") (pintype "passive"))
    )
    (net (code "105") (name "unconnected-(JTAG_STYRI-S-Pad8)") (class "Default")
      (node (ref "JTAG_STYR") (pin "8") (pinfunction "S_8") (pintype "passive"))
    )
    (net (code "106") (name "unconnected-(LINEENABLEMUX1A-X11-Pad20)") (class "Default")
      (node (ref "LINEENABLEMUX1") (pin "20") (pinfunction "X11_20") (pintype "input"))
    )
    (net (code "107") (name "unconnected-(LINEENABLEMUX1A-X12-Pad19)") (class "Default")
      (node (ref "LINEENABLEMUX1") (pin "19") (pinfunction "X12_19") (pintype "input"))
    )
    (net (code "108") (name "unconnected-(LINEENABLEMUX1A-X13-Pad18)") (class "Default")
      (node (ref "LINEENABLEMUX1") (pin "18") (pinfunction "X13_18") (pintype "input"))
    )
    (net (code "109") (name "unconnected-(LINEVALUEMUX1A-X11-Pad20)") (class "Default")
      (node (ref "LINEVALUEMUX1") (pin "20") (pinfunction "X11_20") (pintype "input"))
    )
    (net (code "110") (name "unconnected-(LINEVALUEMUX1A-X12-Pad19)") (class "Default")
      (node (ref "LINEVALUEMUX1") (pin "19") (pinfunction "X12_19") (pintype "input"))
    )
    (net (code "111") (name "unconnected-(LINEVALUEMUX1A-X13-Pad18)") (class "Default")
      (node (ref "LINEVALUEMUX1") (pin "18") (pinfunction "X13_18") (pintype "input"))
    )
    (net (code "112") (name "unconnected-(MOTORB-S-Pad10)") (class "Default")
      (node (ref "MOTOR") (pin "10") (pinfunction "S_10") (pintype "passive"))
    )
    (net (code "113") (name "unconnected-(MOTORC-S-Pad2)") (class "Default")
      (node (ref "MOTOR") (pin "2") (pinfunction "S_2") (pintype "passive"))
    )
    (net (code "114") (name "unconnected-(MOTORD-S-Pad3)") (class "Default")
      (node (ref "MOTOR") (pin "3") (pinfunction "S_3") (pintype "passive"))
    )
    (net (code "115") (name "unconnected-(MOTORE-S-Pad4)") (class "Default")
      (node (ref "MOTOR") (pin "4") (pinfunction "S_4") (pintype "passive"))
    )
    (net (code "116") (name "unconnected-(MOTORJ-S-Pad9)") (class "Default")
      (node (ref "MOTOR") (pin "9") (pinfunction "S_9") (pintype "passive"))
    )
    (net (code "117") (name "unconnected-(SENSOR_LINE1A-S-Pad1)") (class "Default")
      (node (ref "SENSOR_LINE1") (pin "1") (pinfunction "S_1") (pintype "passive"))
    )
    (net (code "118") (name "unconnected-(SENSOR_LINE1B-S-Pad10)") (class "Default")
      (node (ref "SENSOR_LINE1") (pin "10") (pinfunction "S_10") (pintype "passive"))
    )
    (net (code "119") (name "unconnected-(SENSOR_LINE1C-S-Pad11)") (class "Default")
      (node (ref "SENSOR_LINE1") (pin "11") (pinfunction "S_11") (pintype "passive"))
    )
    (net (code "120") (name "unconnected-(SENSOR_LINE1D-S-Pad12)") (class "Default")
      (node (ref "SENSOR_LINE1") (pin "12") (pinfunction "S_12") (pintype "passive"))
    )
    (net (code "121") (name "unconnected-(SENSOR_LINE1E-S-Pad13)") (class "Default")
      (node (ref "SENSOR_LINE1") (pin "13") (pinfunction "S_13") (pintype "passive"))
    )
    (net (code "122") (name "unconnected-(SENSOR_LINE1F-S-Pad14)") (class "Default")
      (node (ref "SENSOR_LINE1") (pin "14") (pinfunction "S_14") (pintype "passive"))
    )
    (net (code "123") (name "unconnected-(SENSOR_LINE1G-S-Pad15)") (class "Default")
      (node (ref "SENSOR_LINE1") (pin "15") (pinfunction "S_15") (pintype "passive"))
    )
    (net (code "124") (name "unconnected-(SENSOR_LINE1H-S-Pad16)") (class "Default")
      (node (ref "SENSOR_LINE1") (pin "16") (pinfunction "S_16") (pintype "passive"))
    )
    (net (code "125") (name "unconnected-(SENSOR_LINE1I-S-Pad17)") (class "Default")
      (node (ref "SENSOR_LINE1") (pin "17") (pinfunction "S_17") (pintype "passive"))
    )
    (net (code "126") (name "unconnected-(SENSOR_LINE1J-S-Pad18)") (class "Default")
      (node (ref "SENSOR_LINE1") (pin "18") (pinfunction "S_18") (pintype "passive"))
    )
    (net (code "127") (name "unconnected-(SENSOR_LINE1K-S-Pad19)") (class "Default")
      (node (ref "SENSOR_LINE1") (pin "19") (pinfunction "S_19") (pintype "passive"))
    )
    (net (code "128") (name "unconnected-(SENSOR_LINE1L-S-Pad2)") (class "Default")
      (node (ref "SENSOR_LINE1") (pin "2") (pinfunction "S_2") (pintype "passive"))
    )
    (net (code "129") (name "unconnected-(SENSOR_LINE1M-S-Pad20)") (class "Default")
      (node (ref "SENSOR_LINE1") (pin "20") (pinfunction "S_20") (pintype "passive"))
    )
    (net (code "130") (name "unconnected-(SENSOR_LINE1N-S-Pad21)") (class "Default")
      (node (ref "SENSOR_LINE1") (pin "21") (pinfunction "S_21") (pintype "passive"))
    )
    (net (code "131") (name "unconnected-(SENSOR_LINE1O-S-Pad22)") (class "Default")
      (node (ref "SENSOR_LINE1") (pin "22") (pinfunction "S_22") (pintype "passive"))
    )
    (net (code "132") (name "unconnected-(SENSOR_LINE1P-S-Pad23)") (class "Default")
      (node (ref "SENSOR_LINE1") (pin "23") (pinfunction "S_23") (pintype "passive"))
    )
    (net (code "133") (name "unconnected-(SENSOR_LINE1S-S-Pad26)") (class "Default")
      (node (ref "SENSOR_LINE1") (pin "26") (pinfunction "S_26") (pintype "passive"))
    )
    (net (code "134") (name "unconnected-(SENSOR_LINE1U-S-Pad4)") (class "Default")
      (node (ref "SENSOR_LINE1") (pin "4") (pinfunction "S_4") (pintype "passive"))
    )
    (net (code "135") (name "unconnected-(SENSOR_LINE1V-S-Pad5)") (class "Default")
      (node (ref "SENSOR_LINE1") (pin "5") (pinfunction "S_5") (pintype "passive"))
    )
    (net (code "136") (name "unconnected-(SENSOR_LINE1X-S-Pad7)") (class "Default")
      (node (ref "SENSOR_LINE1") (pin "7") (pinfunction "S_7") (pintype "passive"))
    )
    (net (code "137") (name "unconnected-(SENSOR_LINE1Y-S-Pad8)") (class "Default")
      (node (ref "SENSOR_LINE1") (pin "8") (pinfunction "S_8") (pintype "passive"))
    )
    (net (code "138") (name "unconnected-(SENSOR_LINE1Z-S-Pad9)") (class "Default")
      (node (ref "SENSOR_LINE1") (pin "9") (pinfunction "S_9") (pintype "passive"))
    )
    (net (code "139") (name "unconnected-(SERVO_UARTB-S-Pad2)") (class "Default")
      (node (ref "SERVO_UART") (pin "2") (pinfunction "S_2") (pintype "passive"))
    )
    (net (code "140") (name "unconnected-(U$2-A2-PadP$3)") (class "Default")
      (node (ref "U$2") (pin "P$3") (pinfunction "A2_P$3") (pintype "bidirectional"))
    )
    (net (code "141") (name "unconnected-(U$2-A3-PadP$4)") (class "Default")
      (node (ref "U$2") (pin "P$4") (pinfunction "A3_P$4") (pintype "bidirectional"))
    )
    (net (code "142") (name "unconnected-(U$2-A4-PadP$5)") (class "Default")
      (node (ref "U$2") (pin "P$5") (pinfunction "A4_P$5") (pintype "bidirectional"))
    )
    (net (code "143") (name "unconnected-(U$2-B2-PadP$12)") (class "Default")
      (node (ref "U$2") (pin "P$12") (pinfunction "B2_P$12") (pintype "bidirectional"))
    )
    (net (code "144") (name "unconnected-(U$2-B3-PadP$11)") (class "Default")
      (node (ref "U$2") (pin "P$11") (pinfunction "B3_P$11") (pintype "bidirectional"))
    )
    (net (code "145") (name "unconnected-(U$2-B4-PadP$10)") (class "Default")
      (node (ref "U$2") (pin "P$10") (pinfunction "B4_P$10") (pintype "bidirectional"))
    )
    (net (code "146") (name "unconnected-(XA-S-Pad1)") (class "Default")
      (node (ref "X") (pin "1") (pinfunction "S_1") (pintype "passive"))
    )
    (net (code "147") (name "unconnected-(XC-S-Pad11)") (class "Default")
      (node (ref "X") (pin "11") (pinfunction "S_11") (pintype "passive"))
    )
    (net (code "148") (name "unconnected-(XE-S-Pad13)") (class "Default")
      (node (ref "X") (pin "13") (pinfunction "S_13") (pintype "passive"))
    )
    (net (code "149") (name "unconnected-(XF-S-Pad14)") (class "Default")
      (node (ref "X") (pin "14") (pinfunction "S_14") (pintype "passive"))
    )
    (net (code "150") (name "unconnected-(XG-S-Pad15)") (class "Default")
      (node (ref "X") (pin "15") (pinfunction "S_15") (pintype "passive"))
    )
    (net (code "151") (name "unconnected-(XI-S-Pad17)") (class "Default")
      (node (ref "X") (pin "17") (pinfunction "S_17") (pintype "passive"))
    )
    (net (code "152") (name "unconnected-(XK-S-Pad19)") (class "Default")
      (node (ref "X") (pin "19") (pinfunction "S_19") (pintype "passive"))
    )
    (net (code "153") (name "unconnected-(XN-S-Pad3)") (class "Default")
      (node (ref "X") (pin "3") (pinfunction "S_3") (pintype "passive"))
    )
    (net (code "154") (name "unconnected-(XO-S-Pad4)") (class "Default")
      (node (ref "X") (pin "4") (pinfunction "S_4") (pintype "passive"))
    )
    (net (code "155") (name "unconnected-(XP-S-Pad5)") (class "Default")
      (node (ref "X") (pin "5") (pinfunction "S_5") (pintype "passive"))
    )
    (net (code "156") (name "unconnected-(XQ-S-Pad6)") (class "Default")
      (node (ref "X") (pin "6") (pinfunction "S_6") (pintype "passive"))
    )
    (net (code "157") (name "unconnected-(XR-S-Pad7)") (class "Default")
      (node (ref "X") (pin "7") (pinfunction "S_7") (pintype "passive"))
    )
    (net (code "158") (name "unconnected-(XT-S-Pad9)") (class "Default")
      (node (ref "X") (pin "9") (pinfunction "S_9") (pintype "passive"))
    )
  )
)
